# olliduino.net
KiCad netlist of a schematic drawn in EAGLE
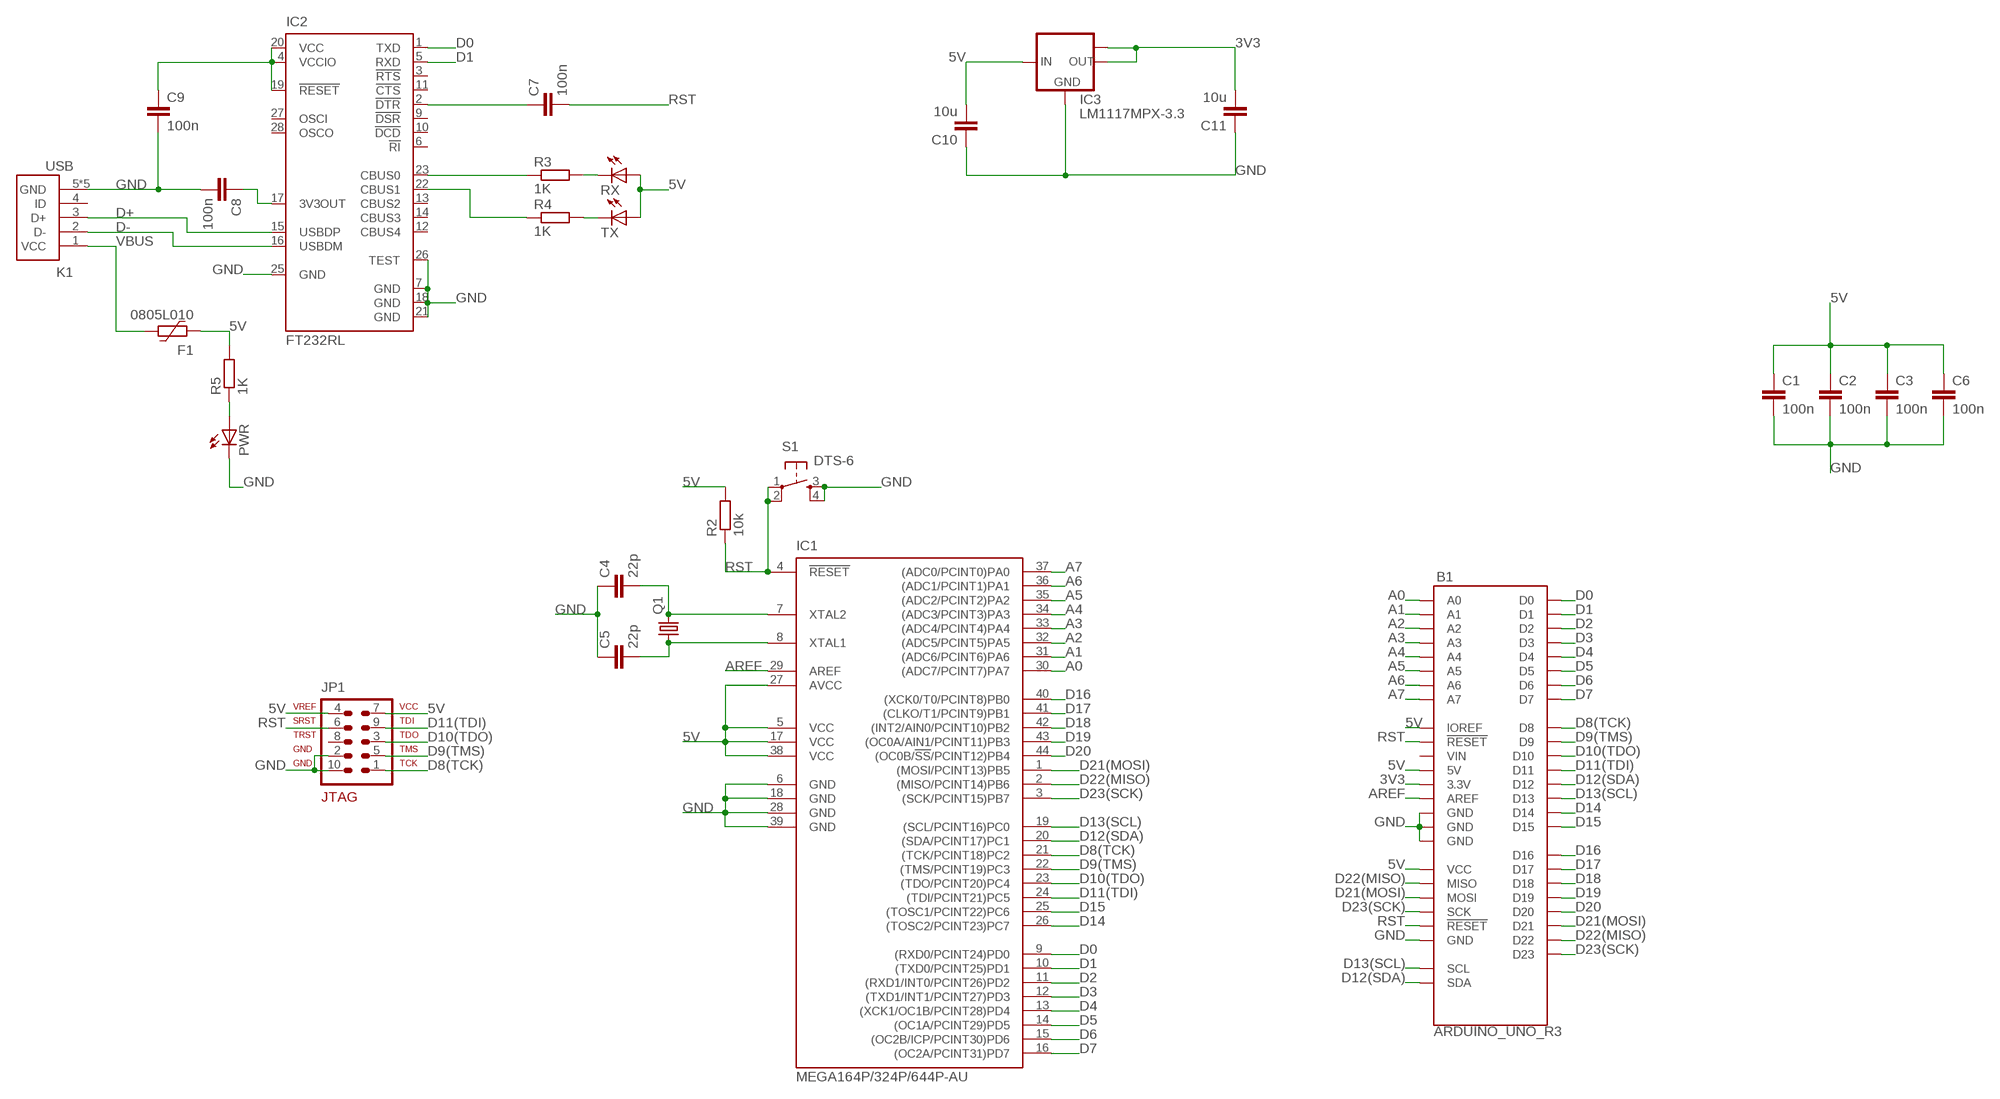
[diagram p0: schematic, sheet 1]

(export (version "E")
  (design (tool "Eeschema 10.0.6"))
  (components
    (comp (ref "B1")
      (value "ARDUINO_UNO_R3")
      (footprint "eagle-import:ARDUINO_R3")
      (libsource (lib "eagle-import") (part "ARDUINO_UNO_R3"))
    )
    (comp (ref "C1")
      (value "100n")
      (footprint "eagle-import:C0805")
      (libsource (lib "eagle-import") (part "C-EUC0805"))
    )
    (comp (ref "C2")
      (value "100n")
      (footprint "eagle-import:C0805")
      (libsource (lib "eagle-import") (part "C-EUC0805"))
    )
    (comp (ref "C3")
      (value "100n")
      (footprint "eagle-import:C0805")
      (libsource (lib "eagle-import") (part "C-EUC0805"))
    )
    (comp (ref "C4")
      (value "22p")
      (footprint "eagle-import:C0805")
      (libsource (lib "eagle-import") (part "C-EUC0805"))
    )
    (comp (ref "C5")
      (value "22p")
      (footprint "eagle-import:C0805")
      (libsource (lib "eagle-import") (part "C-EUC0805"))
    )
    (comp (ref "C6")
      (value "100n")
      (footprint "eagle-import:C0805")
      (libsource (lib "eagle-import") (part "C-EUC0805"))
    )
    (comp (ref "C7")
      (value "100n")
      (footprint "eagle-import:C0805")
      (libsource (lib "eagle-import") (part "C-EUC0805"))
    )
    (comp (ref "C8")
      (value "100n")
      (footprint "eagle-import:C0805")
      (libsource (lib "eagle-import") (part "C-EUC0805"))
    )
    (comp (ref "C9")
      (value "100n")
      (footprint "eagle-import:C0805")
      (libsource (lib "eagle-import") (part "C-EUC0805"))
    )
    (comp (ref "C10")
      (value "10u")
      (footprint "eagle-import:C0805")
      (libsource (lib "eagle-import") (part "C-EUC0805"))
    )
    (comp (ref "C11")
      (value "10u")
      (footprint "eagle-import:C0805")
      (libsource (lib "eagle-import") (part "C-EUC0805"))
    )
    (comp (ref "F1")
      (value "0805L010")
      (footprint "eagle-import:0805L")
      (fields (field (name "MF") "Littelfuse"))
      (libsource (lib "eagle-import") (part "?0805L010"))
    )
    (comp (ref "IC1")
      (value "MEGA164P/324P/644P-AU")
      (footprint "eagle-import:TQFP44")
      (libsource (lib "eagle-import") (part "MEGA164P/324P/644P-AU"))
    )
    (comp (ref "IC2")
      (value "FT232RL")
      (footprint "eagle-import:SSOP28")
      (libsource (lib "eagle-import") (part "FT232RL"))
    )
    (comp (ref "IC3")
      (value "LM1117MPX-3.3")
      (footprint "eagle-import:SOT223")
      (libsource (lib "eagle-import") (part "LM1117MPX-3.3"))
    )
    (comp (ref "JP1")
      (value "AVR-JTAG-10")
      (footprint "eagle-import:AVR-JTAG-10")
      (libsource (lib "eagle-import") (part "AVR-JTAG-10"))
    )
    (comp (ref "K1")
      (value "USB")
      (footprint "eagle-import:651005136521")
      (libsource (lib "eagle-import") (part "651005136521"))
    )
    (comp (ref "PWR")
      (value "LEDCHIPLED_0805")
      (footprint "eagle-import:CHIPLED_0805")
      (libsource (lib "eagle-import") (part "LEDCHIPLED_0805"))
    )
    (comp (ref "Q1")
      (value "CRYSTALHC49U-V")
      (footprint "eagle-import:HC49U-V")
      (libsource (lib "eagle-import") (part "CRYSTALHC49U-V"))
    )
    (comp (ref "R2")
      (value "10k")
      (footprint "eagle-import:M0805")
      (libsource (lib "eagle-import") (part "R-EU_M0805"))
    )
    (comp (ref "R3")
      (value "1K")
      (footprint "eagle-import:M0805")
      (libsource (lib "eagle-import") (part "R-EU_M0805"))
    )
    (comp (ref "R4")
      (value "1K")
      (footprint "eagle-import:M0805")
      (libsource (lib "eagle-import") (part "R-EU_M0805"))
    )
    (comp (ref "R5")
      (value "1K")
      (footprint "eagle-import:M0805")
      (libsource (lib "eagle-import") (part "R-EU_M0805"))
    )
    (comp (ref "RX")
      (value "LEDCHIPLED_0805")
      (footprint "eagle-import:CHIPLED_0805")
      (libsource (lib "eagle-import") (part "LEDCHIPLED_0805"))
    )
    (comp (ref "S1")
      (value "DTS-6")
      (footprint "eagle-import:DTS-6")
      (libsource (lib "eagle-import") (part "DTS-6"))
    )
    (comp (ref "TX")
      (value "LEDCHIPLED_0805")
      (footprint "eagle-import:CHIPLED_0805")
      (libsource (lib "eagle-import") (part "LEDCHIPLED_0805"))
    )
  )
  (nets
    (net (code "1") (name "/3V3") (class "Default")
      (node (ref "B1") (pin "3.3V") (pinfunction "3.3V_3.3V") (pintype "bidirectional"))
      (node (ref "C11") (pin "2") (pinfunction "2_2") (pintype "passive"))
      (node (ref "IC3") (pin "2") (pinfunction "OUT_2") (pintype "passive"))
      (node (ref "IC3") (pin "TAB") (pinfunction "OUT1_TAB") (pintype "passive"))
    )
    (net (code "2") (name "/5V") (class "Default")
      (node (ref "B1") (pin "5V") (pinfunction "5V_5V") (pintype "bidirectional"))
      (node (ref "B1") (pin "IOREF") (pinfunction "IOREF_IOREF") (pintype "bidirectional"))
      (node (ref "B1") (pin "VCC") (pinfunction "VCC_VCC") (pintype "bidirectional"))
      (node (ref "C1") (pin "1") (pinfunction "1_1") (pintype "passive"))
      (node (ref "C10") (pin "2") (pinfunction "2_2") (pintype "passive"))
      (node (ref "C2") (pin "1") (pinfunction "1_1") (pintype "passive"))
      (node (ref "C3") (pin "1") (pinfunction "1_1") (pintype "passive"))
      (node (ref "C6") (pin "1") (pinfunction "1_1") (pintype "passive"))
      (node (ref "C9") (pin "1") (pinfunction "1_1") (pintype "passive"))
      (node (ref "F1") (pin "2") (pinfunction "2_2") (pintype "passive"))
      (node (ref "IC1") (pin "17") (pinfunction "VCC_17") (pintype "power_in"))
      (node (ref "IC1") (pin "27") (pinfunction "AVCC_27") (pintype "power_in"))
      (node (ref "IC1") (pin "38") (pinfunction "VCC_38") (pintype "power_in"))
      (node (ref "IC1") (pin "5") (pinfunction "VCC_5") (pintype "power_in"))
      (node (ref "IC2") (pin "19") (pinfunction "~{RESET}_19") (pintype "input"))
      (node (ref "IC2") (pin "20") (pinfunction "VCC_20") (pintype "power_in"))
      (node (ref "IC2") (pin "4") (pinfunction "VCCIO_4") (pintype "power_in"))
      (node (ref "IC3") (pin "3") (pinfunction "IN_3") (pintype "input"))
      (node (ref "JP1") (pin "4") (pinfunction "4_4") (pintype "passive"))
      (node (ref "JP1") (pin "7") (pinfunction "7_7") (pintype "passive"))
      (node (ref "R2") (pin "2") (pinfunction "2_2") (pintype "passive"))
      (node (ref "R5") (pin "2") (pinfunction "2_2") (pintype "passive"))
      (node (ref "RX") (pin "A") (pinfunction "A_A") (pintype "passive"))
      (node (ref "TX") (pin "A") (pinfunction "A_A") (pintype "passive"))
    )
    (net (code "3") (name "/A0") (class "Default")
      (node (ref "B1") (pin "A0") (pinfunction "A0_A0") (pintype "bidirectional"))
      (node (ref "IC1") (pin "30") (pinfunction "(ADC7/PCINT7)PA7_30") (pintype "bidirectional"))
    )
    (net (code "4") (name "/A1") (class "Default")
      (node (ref "B1") (pin "A1") (pinfunction "A1_A1") (pintype "bidirectional"))
      (node (ref "IC1") (pin "31") (pinfunction "(ADC6/PCINT6)PA6_31") (pintype "bidirectional"))
    )
    (net (code "5") (name "/A2") (class "Default")
      (node (ref "B1") (pin "A2") (pinfunction "A2_A2") (pintype "bidirectional"))
      (node (ref "IC1") (pin "32") (pinfunction "(ADC5/PCINT5)PA5_32") (pintype "bidirectional"))
    )
    (net (code "6") (name "/A3") (class "Default")
      (node (ref "B1") (pin "A3") (pinfunction "A3_A3") (pintype "bidirectional"))
      (node (ref "IC1") (pin "33") (pinfunction "(ADC4/PCINT4)PA4_33") (pintype "bidirectional"))
    )
    (net (code "7") (name "/A4") (class "Default")
      (node (ref "B1") (pin "A4") (pinfunction "A4_A4") (pintype "bidirectional"))
      (node (ref "IC1") (pin "34") (pinfunction "(ADC3/PCINT3)PA3_34") (pintype "bidirectional"))
    )
    (net (code "8") (name "/A5") (class "Default")
      (node (ref "B1") (pin "A5") (pinfunction "A5_A5") (pintype "bidirectional"))
      (node (ref "IC1") (pin "35") (pinfunction "(ADC2/PCINT2)PA2_35") (pintype "bidirectional"))
    )
    (net (code "9") (name "/A6") (class "Default")
      (node (ref "B1") (pin "A6") (pinfunction "A6_A6") (pintype "bidirectional"))
      (node (ref "IC1") (pin "36") (pinfunction "(ADC1/PCINT1)PA1_36") (pintype "bidirectional"))
    )
    (net (code "10") (name "/A7") (class "Default")
      (node (ref "B1") (pin "A7") (pinfunction "A7_A7") (pintype "bidirectional"))
      (node (ref "IC1") (pin "37") (pinfunction "(ADC0/PCINT0)PA0_37") (pintype "bidirectional"))
    )
    (net (code "11") (name "/AREF") (class "Default")
      (node (ref "B1") (pin "AREF") (pinfunction "AREF_AREF") (pintype "bidirectional"))
      (node (ref "IC1") (pin "29") (pinfunction "AREF_29") (pintype "power_in"))
    )
    (net (code "12") (name "/D+") (class "Default")
      (node (ref "IC2") (pin "15") (pinfunction "USBDP_15") (pintype "bidirectional"))
      (node (ref "K1") (pin "3") (pinfunction "D+_3") (pintype "passive"))
    )
    (net (code "13") (name "/D-") (class "Default")
      (node (ref "IC2") (pin "16") (pinfunction "USBDM_16") (pintype "bidirectional"))
      (node (ref "K1") (pin "2") (pinfunction "D-_2") (pintype "passive"))
    )
    (net (code "14") (name "/D0") (class "Default")
      (node (ref "B1") (pin "D0") (pinfunction "D0_D0") (pintype "bidirectional"))
      (node (ref "IC1") (pin "9") (pinfunction "(RXD0/PCINT24)PD0_9") (pintype "bidirectional"))
      (node (ref "IC2") (pin "1") (pinfunction "TXD_1") (pintype "output"))
    )
    (net (code "15") (name "/D1") (class "Default")
      (node (ref "B1") (pin "D1") (pinfunction "D1_D1") (pintype "bidirectional"))
      (node (ref "IC1") (pin "10") (pinfunction "(TXD0/PCINT25)PD1_10") (pintype "bidirectional"))
      (node (ref "IC2") (pin "5") (pinfunction "RXD_5") (pintype "input"))
    )
    (net (code "16") (name "/D2") (class "Default")
      (node (ref "B1") (pin "D2") (pinfunction "D2_D2") (pintype "bidirectional"))
      (node (ref "IC1") (pin "11") (pinfunction "(RXD1/INT0/PCINT26)PD2_11") (pintype "bidirectional"))
    )
    (net (code "17") (name "/D3") (class "Default")
      (node (ref "B1") (pin "D3") (pinfunction "D3_D3") (pintype "bidirectional"))
      (node (ref "IC1") (pin "12") (pinfunction "(TXD1/INT1/PCINT27)PD3_12") (pintype "bidirectional"))
    )
    (net (code "18") (name "/D4") (class "Default")
      (node (ref "B1") (pin "D4") (pinfunction "D4_D4") (pintype "bidirectional"))
      (node (ref "IC1") (pin "13") (pinfunction "(XCK1/OC1B/PCINT28)PD4_13") (pintype "bidirectional"))
    )
    (net (code "19") (name "/D5") (class "Default")
      (node (ref "B1") (pin "D5") (pinfunction "D5_D5") (pintype "bidirectional"))
      (node (ref "IC1") (pin "14") (pinfunction "(OC1A/PCINT29)PD5_14") (pintype "bidirectional"))
    )
    (net (code "20") (name "/D6") (class "Default")
      (node (ref "B1") (pin "D6") (pinfunction "D6_D6") (pintype "bidirectional"))
      (node (ref "IC1") (pin "15") (pinfunction "(OC2B/ICP/PCINT30)PD6_15") (pintype "bidirectional"))
    )
    (net (code "21") (name "/D7") (class "Default")
      (node (ref "B1") (pin "D7") (pinfunction "D7_D7") (pintype "bidirectional"))
      (node (ref "IC1") (pin "16") (pinfunction "(OC2A/PCINT31)PD7_16") (pintype "bidirectional"))
    )
    (net (code "22") (name "/D8(TCK)") (class "Default")
      (node (ref "B1") (pin "D8") (pinfunction "D8_D8") (pintype "bidirectional"))
      (node (ref "IC1") (pin "21") (pinfunction "(TCK/PCINT18)PC2_21") (pintype "bidirectional"))
      (node (ref "JP1") (pin "1") (pinfunction "1_1") (pintype "passive"))
    )
    (net (code "23") (name "/D9(TMS)") (class "Default")
      (node (ref "B1") (pin "D9") (pinfunction "D9_D9") (pintype "bidirectional"))
      (node (ref "IC1") (pin "22") (pinfunction "(TMS/PCINT19)PC3_22") (pintype "bidirectional"))
      (node (ref "JP1") (pin "5") (pinfunction "5_5") (pintype "passive"))
    )
    (net (code "24") (name "/D10(TDO)") (class "Default")
      (node (ref "B1") (pin "D10") (pinfunction "D10_D10") (pintype "bidirectional"))
      (node (ref "IC1") (pin "23") (pinfunction "(TDO/PCINT20)PC4_23") (pintype "bidirectional"))
      (node (ref "JP1") (pin "3") (pinfunction "3_3") (pintype "passive"))
    )
    (net (code "25") (name "/D11(TDI)") (class "Default")
      (node (ref "B1") (pin "D11") (pinfunction "D11_D11") (pintype "bidirectional"))
      (node (ref "IC1") (pin "24") (pinfunction "(TDI/PCINT21)PC5_24") (pintype "bidirectional"))
      (node (ref "JP1") (pin "9") (pinfunction "9_9") (pintype "passive"))
    )
    (net (code "26") (name "/D12(SDA)") (class "Default")
      (node (ref "B1") (pin "D12") (pinfunction "D12_D12") (pintype "bidirectional"))
      (node (ref "B1") (pin "SDA") (pinfunction "SDA_SDA") (pintype "bidirectional"))
      (node (ref "IC1") (pin "20") (pinfunction "(SDA/PCINT17)PC1_20") (pintype "bidirectional"))
    )
    (net (code "27") (name "/D13(SCL)") (class "Default")
      (node (ref "B1") (pin "D13") (pinfunction "D13_D13") (pintype "bidirectional"))
      (node (ref "B1") (pin "SCL") (pinfunction "SCL_SCL") (pintype "bidirectional"))
      (node (ref "IC1") (pin "19") (pinfunction "(SCL/PCINT16)PC0_19") (pintype "bidirectional"))
    )
    (net (code "28") (name "/D14") (class "Default")
      (node (ref "B1") (pin "D14") (pinfunction "D14_D14") (pintype "bidirectional"))
      (node (ref "IC1") (pin "26") (pinfunction "(TOSC2/PCINT23)PC7_26") (pintype "bidirectional"))
    )
    (net (code "29") (name "/D15") (class "Default")
      (node (ref "B1") (pin "D15") (pinfunction "D15_D15") (pintype "bidirectional"))
      (node (ref "IC1") (pin "25") (pinfunction "(TOSC1/PCINT22)PC6_25") (pintype "bidirectional"))
    )
    (net (code "30") (name "/D16") (class "Default")
      (node (ref "B1") (pin "D16") (pinfunction "D16_D16") (pintype "bidirectional"))
      (node (ref "IC1") (pin "40") (pinfunction "(XCK0/T0/PCINT8)PB0_40") (pintype "bidirectional"))
    )
    (net (code "31") (name "/D17") (class "Default")
      (node (ref "B1") (pin "D17") (pinfunction "D17_D17") (pintype "bidirectional"))
      (node (ref "IC1") (pin "41") (pinfunction "(CLKO/T1/PCINT9)PB1_41") (pintype "bidirectional"))
    )
    (net (code "32") (name "/D18") (class "Default")
      (node (ref "B1") (pin "D18") (pinfunction "D18_D18") (pintype "bidirectional"))
      (node (ref "IC1") (pin "42") (pinfunction "(INT2/AIN0/PCINT10)PB2_42") (pintype "bidirectional"))
    )
    (net (code "33") (name "/D19") (class "Default")
      (node (ref "B1") (pin "D19") (pinfunction "D19_D19") (pintype "bidirectional"))
      (node (ref "IC1") (pin "43") (pinfunction "(OC0A/AIN1/PCINT11)PB3_43") (pintype "bidirectional"))
    )
    (net (code "34") (name "/D20") (class "Default")
      (node (ref "B1") (pin "D20") (pinfunction "D20_D20") (pintype "bidirectional"))
      (node (ref "IC1") (pin "44") (pinfunction "(OC0B/~{SS}/PCINT12)PB4_44") (pintype "bidirectional"))
    )
    (net (code "35") (name "/D21(MOSI)") (class "Default")
      (node (ref "B1") (pin "D21") (pinfunction "D21_D21") (pintype "bidirectional"))
      (node (ref "B1") (pin "MOSI") (pinfunction "MOSI_MOSI") (pintype "bidirectional"))
      (node (ref "IC1") (pin "1") (pinfunction "(MOSI/PCINT13)PB5_1") (pintype "bidirectional"))
    )
    (net (code "36") (name "/D22(MISO)") (class "Default")
      (node (ref "B1") (pin "D22") (pinfunction "D22_D22") (pintype "bidirectional"))
      (node (ref "B1") (pin "MISO") (pinfunction "MISO_MISO") (pintype "bidirectional"))
      (node (ref "IC1") (pin "2") (pinfunction "(MISO/PCINT14)PB6_2") (pintype "bidirectional"))
    )
    (net (code "37") (name "/D23(SCK)") (class "Default")
      (node (ref "B1") (pin "D23") (pinfunction "D23_D23") (pintype "bidirectional"))
      (node (ref "B1") (pin "SCK") (pinfunction "SCK_SCK") (pintype "bidirectional"))
      (node (ref "IC1") (pin "3") (pinfunction "(SCK/PCINT15)PB7_3") (pintype "bidirectional"))
    )
    (net (code "38") (name "/GND") (class "Default")
      (node (ref "B1") (pin "GND@1") (pinfunction "GND_GND@1") (pintype "bidirectional"))
      (node (ref "B1") (pin "GND@2") (pinfunction "GND_GND@2") (pintype "bidirectional"))
      (node (ref "B1") (pin "GND@3") (pinfunction "GND_GND@3") (pintype "bidirectional"))
      (node (ref "B1") (pin "GND@4") (pinfunction "GND_GND@4") (pintype "bidirectional"))
      (node (ref "C1") (pin "2") (pinfunction "2_2") (pintype "passive"))
      (node (ref "C10") (pin "1") (pinfunction "1_1") (pintype "passive"))
      (node (ref "C11") (pin "1") (pinfunction "1_1") (pintype "passive"))
      (node (ref "C2") (pin "2") (pinfunction "2_2") (pintype "passive"))
      (node (ref "C3") (pin "2") (pinfunction "2_2") (pintype "passive"))
      (node (ref "C4") (pin "1") (pinfunction "1_1") (pintype "passive"))
      (node (ref "C5") (pin "1") (pinfunction "1_1") (pintype "passive"))
      (node (ref "C6") (pin "2") (pinfunction "2_2") (pintype "passive"))
      (node (ref "C8") (pin "2") (pinfunction "2_2") (pintype "passive"))
      (node (ref "C9") (pin "2") (pinfunction "2_2") (pintype "passive"))
      (node (ref "IC1") (pin "18") (pinfunction "GND_18") (pintype "power_in"))
      (node (ref "IC1") (pin "28") (pinfunction "GND_28") (pintype "power_in"))
      (node (ref "IC1") (pin "39") (pinfunction "GND_39") (pintype "power_in"))
      (node (ref "IC1") (pin "6") (pinfunction "GND_6") (pintype "power_in"))
      (node (ref "IC2") (pin "18") (pinfunction "GND_18") (pintype "power_in"))
      (node (ref "IC2") (pin "21") (pinfunction "GND_21") (pintype "power_in"))
      (node (ref "IC2") (pin "25") (pinfunction "GND_25") (pintype "power_in"))
      (node (ref "IC2") (pin "26") (pinfunction "TEST_26") (pintype "input"))
      (node (ref "IC2") (pin "7") (pinfunction "GND_7") (pintype "power_in"))
      (node (ref "IC3") (pin "1") (pinfunction "GND_1") (pintype "input"))
      (node (ref "JP1") (pin "10") (pinfunction "10_10") (pintype "passive"))
      (node (ref "JP1") (pin "2") (pinfunction "2_2") (pintype "passive"))
      (node (ref "K1") (pin "5") (pinfunction "GND_5") (pintype "passive"))
      (node (ref "K1") (pin "6") (pinfunction "GND_6") (pintype "passive"))
      (node (ref "K1") (pin "7") (pinfunction "GND_7") (pintype "passive"))
      (node (ref "K1") (pin "8") (pinfunction "GND_8") (pintype "passive"))
      (node (ref "K1") (pin "9") (pinfunction "GND_9") (pintype "passive"))
      (node (ref "PWR") (pin "C") (pinfunction "C_C") (pintype "passive"))
      (node (ref "S1") (pin "3") (pinfunction "3_3") (pintype "passive"))
      (node (ref "S1") (pin "4") (pinfunction "4_4") (pintype "passive"))
    )
    (net (code "39") (name "/RST") (class "Default")
      (node (ref "B1") (pin "RESET@1") (pinfunction "~{RESET}_RESET@1") (pintype "bidirectional"))
      (node (ref "B1") (pin "RESET@2") (pinfunction "~{RESET}_RESET@2") (pintype "bidirectional"))
      (node (ref "C7") (pin "2") (pinfunction "2_2") (pintype "passive"))
      (node (ref "IC1") (pin "4") (pinfunction "~{RESET}_4") (pintype "input"))
      (node (ref "JP1") (pin "6") (pinfunction "6_6") (pintype "passive"))
      (node (ref "R2") (pin "1") (pinfunction "1_1") (pintype "passive"))
      (node (ref "S1") (pin "1") (pinfunction "1_1") (pintype "passive"))
      (node (ref "S1") (pin "2") (pinfunction "2_2") (pintype "passive"))
    )
    (net (code "40") (name "/VBUS") (class "Default")
      (node (ref "F1") (pin "1") (pinfunction "1_1") (pintype "passive"))
      (node (ref "K1") (pin "1") (pinfunction "VCC_1") (pintype "passive"))
    )
    (net (code "41") (name "Net-(IC1-XTAL1)") (class "Default")
      (node (ref "C5") (pin "2") (pinfunction "2_2") (pintype "passive"))
      (node (ref "IC1") (pin "8") (pinfunction "XTAL1_8") (pintype "input"))
      (node (ref "Q1") (pin "1") (pinfunction "1_1") (pintype "passive"))
    )
    (net (code "42") (name "Net-(IC1-XTAL2)") (class "Default")
      (node (ref "C4") (pin "2") (pinfunction "2_2") (pintype "passive"))
      (node (ref "IC1") (pin "7") (pinfunction "XTAL2_7") (pintype "output"))
      (node (ref "Q1") (pin "2") (pinfunction "2_2") (pintype "passive"))
    )
    (net (code "43") (name "Net-(IC2-3V3OUT)") (class "Default")
      (node (ref "C8") (pin "1") (pinfunction "1_1") (pintype "passive"))
      (node (ref "IC2") (pin "17") (pinfunction "3V3OUT_17") (pintype "output"))
    )
    (net (code "44") (name "Net-(IC2-CBUS0)") (class "Default")
      (node (ref "IC2") (pin "23") (pinfunction "CBUS0_23") (pintype "bidirectional"))
      (node (ref "R3") (pin "1") (pinfunction "1_1") (pintype "passive"))
    )
    (net (code "45") (name "Net-(IC2-CBUS1)") (class "Default")
      (node (ref "IC2") (pin "22") (pinfunction "CBUS1_22") (pintype "bidirectional"))
      (node (ref "R4") (pin "1") (pinfunction "1_1") (pintype "passive"))
    )
    (net (code "46") (name "Net-(IC2-~{DTR})") (class "Default")
      (node (ref "C7") (pin "1") (pinfunction "1_1") (pintype "passive"))
      (node (ref "IC2") (pin "2") (pinfunction "~{DTR}_2") (pintype "output"))
    )
    (net (code "47") (name "Net-(PWR-PadA)") (class "Default")
      (node (ref "PWR") (pin "A") (pinfunction "A_A") (pintype "passive"))
      (node (ref "R5") (pin "1") (pinfunction "1_1") (pintype "passive"))
    )
    (net (code "48") (name "Net-(R3-Pad2)") (class "Default")
      (node (ref "R3") (pin "2") (pinfunction "2_2") (pintype "passive"))
      (node (ref "RX") (pin "C") (pinfunction "C_C") (pintype "passive"))
    )
    (net (code "49") (name "Net-(R4-Pad2)") (class "Default")
      (node (ref "R4") (pin "2") (pinfunction "2_2") (pintype "passive"))
      (node (ref "TX") (pin "C") (pinfunction "C_C") (pintype "passive"))
    )
    (net (code "50") (name "unconnected-(B1-PadVIN)") (class "Default")
      (node (ref "B1") (pin "VIN") (pinfunction "VIN_VIN") (pintype "bidirectional"))
    )
    (net (code "51") (name "unconnected-(IC2-CBUS2-Pad13)") (class "Default")
      (node (ref "IC2") (pin "13") (pinfunction "CBUS2_13") (pintype "bidirectional"))
    )
    (net (code "52") (name "unconnected-(IC2-CBUS3-Pad14)") (class "Default")
      (node (ref "IC2") (pin "14") (pinfunction "CBUS3_14") (pintype "bidirectional"))
    )
    (net (code "53") (name "unconnected-(IC2-CBUS4-Pad12)") (class "Default")
      (node (ref "IC2") (pin "12") (pinfunction "CBUS4_12") (pintype "bidirectional"))
    )
    (net (code "54") (name "unconnected-(IC2-OSCI-Pad27)") (class "Default")
      (node (ref "IC2") (pin "27") (pinfunction "OSCI_27") (pintype "input"))
    )
    (net (code "55") (name "unconnected-(IC2-OSCO-Pad28)") (class "Default")
      (node (ref "IC2") (pin "28") (pinfunction "OSCO_28") (pintype "output"))
    )
    (net (code "56") (name "unconnected-(IC2-~{CTS}-Pad11)") (class "Default")
      (node (ref "IC2") (pin "11") (pinfunction "~{CTS}_11") (pintype "input"))
    )
    (net (code "57") (name "unconnected-(IC2-~{DCD}-Pad10)") (class "Default")
      (node (ref "IC2") (pin "10") (pinfunction "~{DCD}_10") (pintype "input"))
    )
    (net (code "58") (name "unconnected-(IC2-~{DSR}-Pad9)") (class "Default")
      (node (ref "IC2") (pin "9") (pinfunction "~{DSR}_9") (pintype "input"))
    )
    (net (code "59") (name "unconnected-(IC2-~{RI}-Pad6)") (class "Default")
      (node (ref "IC2") (pin "6") (pinfunction "~{RI}_6") (pintype "input"))
    )
    (net (code "60") (name "unconnected-(IC2-~{RTS}-Pad3)") (class "Default")
      (node (ref "IC2") (pin "3") (pinfunction "~{RTS}_3") (pintype "output"))
    )
    (net (code "61") (name "unconnected-(JP1-Pad8)") (class "Default")
      (node (ref "JP1") (pin "8") (pinfunction "8_8") (pintype "passive"))
    )
    (net (code "62") (name "unconnected-(K1-ID-Pad4)") (class "Default")
      (node (ref "K1") (pin "4") (pinfunction "ID_4") (pintype "passive"))
    )
  )
)
